# FMC_HPC1.net
KiCad netlist of a schematic drawn in Altium Designer
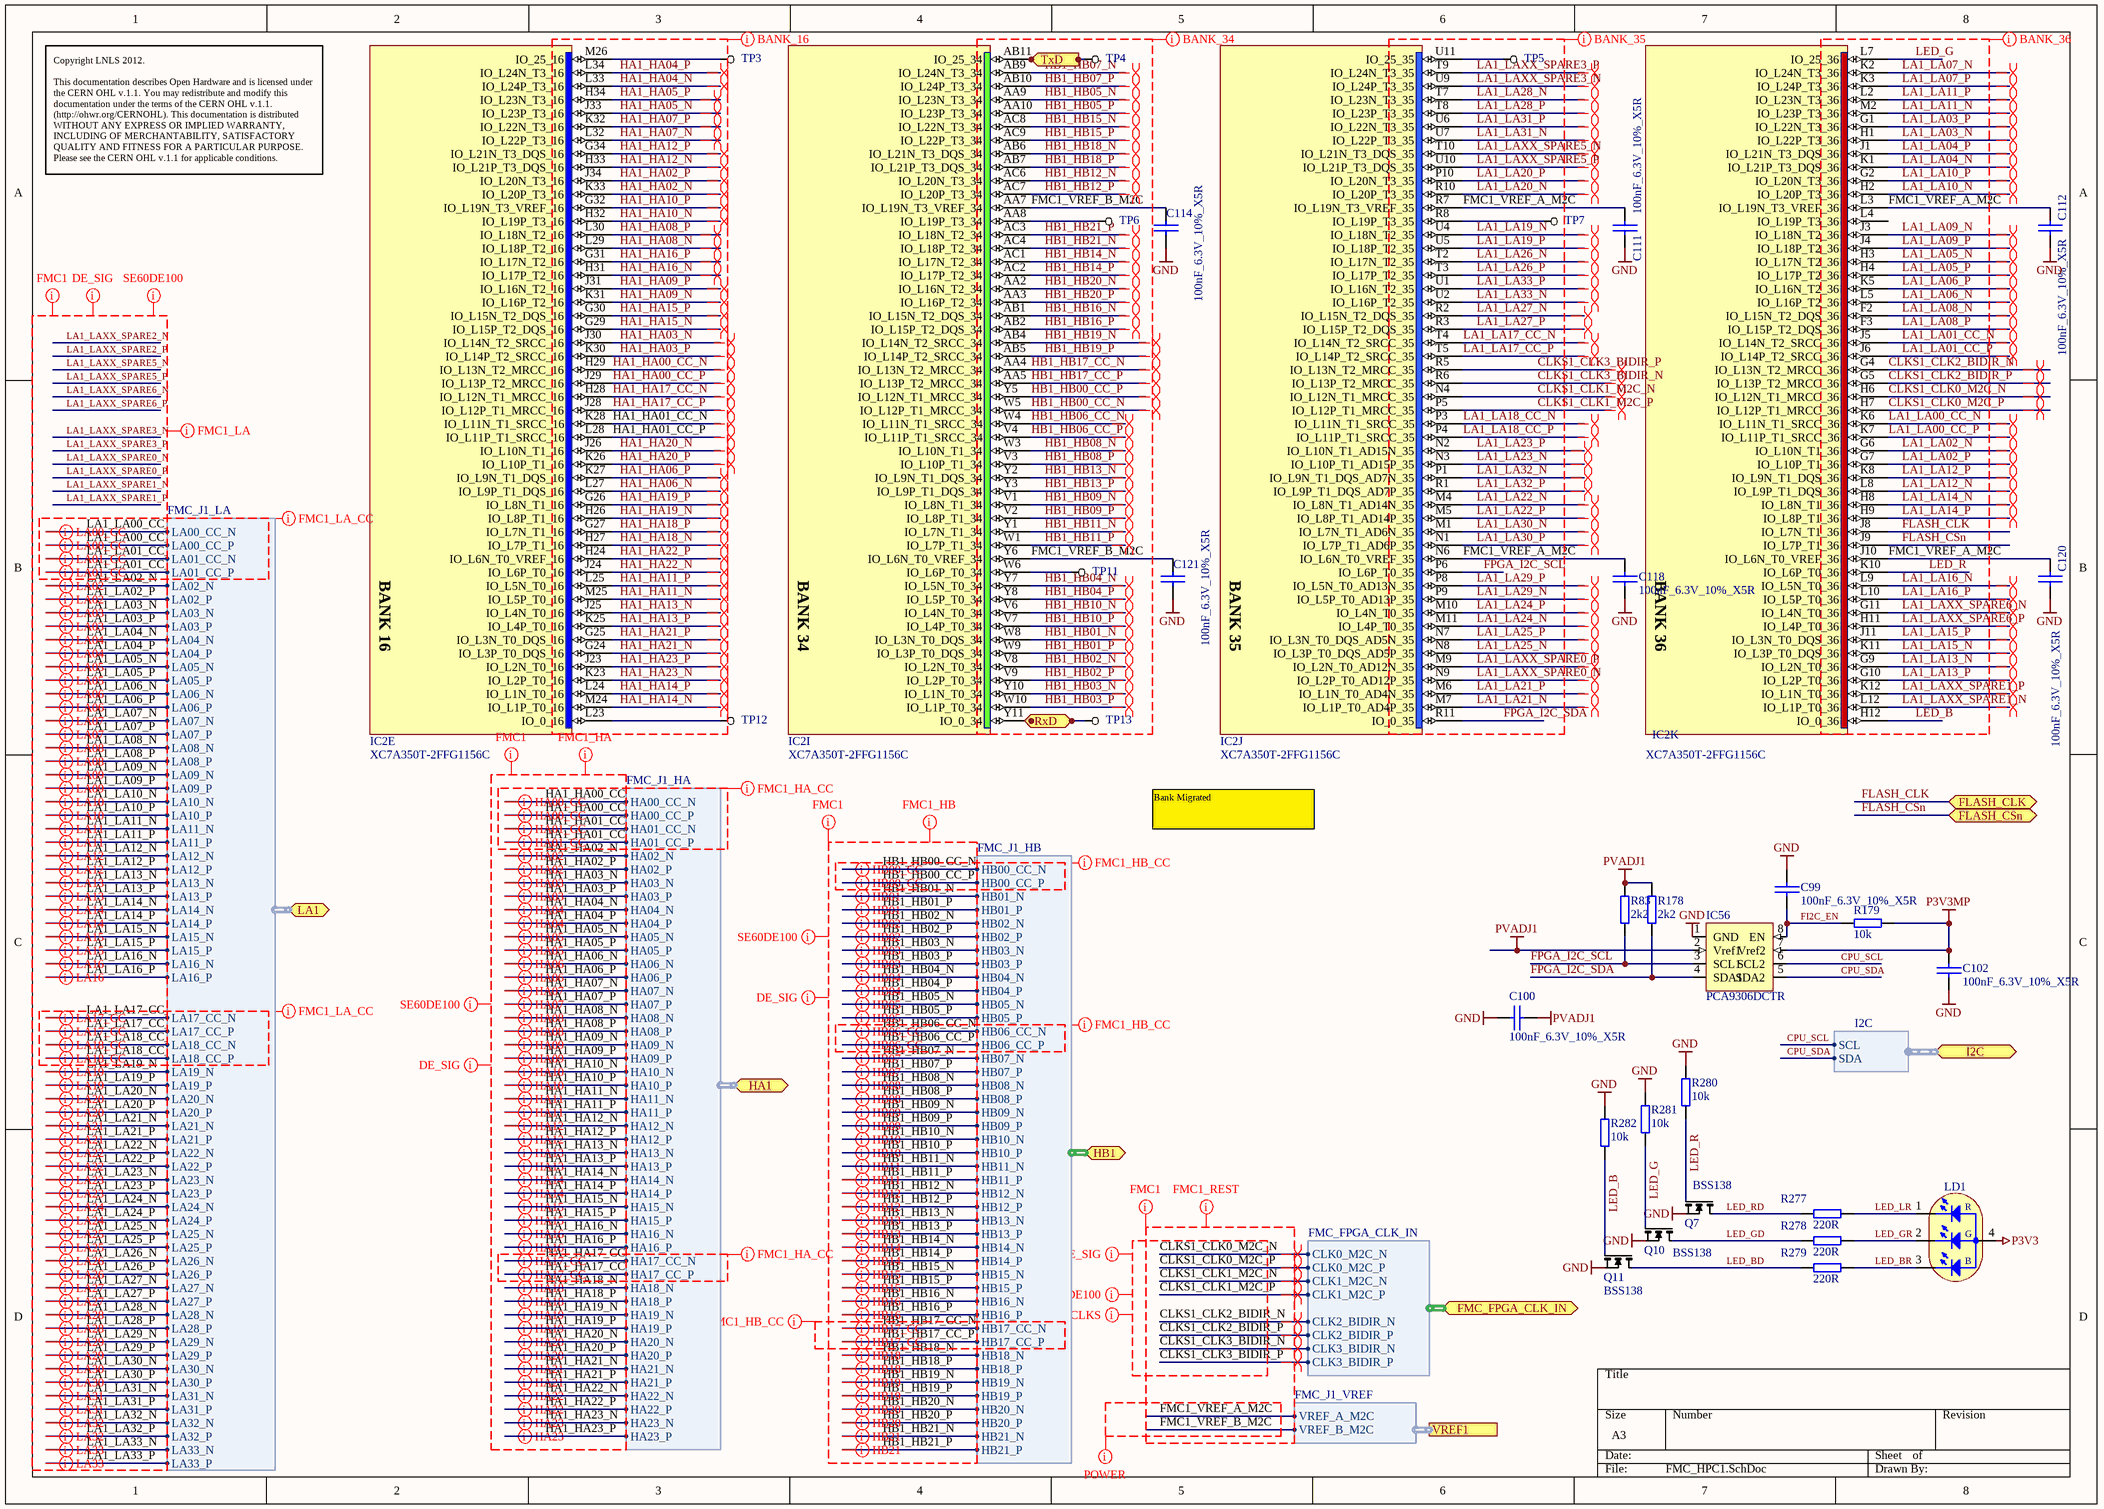
[diagram p0: FMC_HPC1.SchDoc]

(export (version "E")
  (design (tool "Eeschema 10.0.6"))
  (components
    (comp (ref "C99")
      (value "100nF_6.3V_10%_X5R")
      (footprint "0201C")
      (description "Capacitor SMD")
      (libsource (lib "LIBRARY_SCH") (part "CAP_SMD_0201"))
    )
    (comp (ref "C100")
      (value "100nF_6.3V_10%_X5R")
      (footprint "0201C")
      (description "Capacitor SMD")
      (libsource (lib "LIBRARY_SCH") (part "CAP_SMD_0201"))
    )
    (comp (ref "C102")
      (value "100nF_6.3V_10%_X5R")
      (footprint "0201C")
      (description "Capacitor SMD")
      (libsource (lib "LIBRARY_SCH") (part "CAP_SMD_0201"))
    )
    (comp (ref "C111")
      (value "100nF_6.3V_10%_X5R")
      (footprint "0201C")
      (description "Capacitor SMD")
      (libsource (lib "LIBRARY_SCH") (part "CAP_SMD_0201"))
    )
    (comp (ref "C112")
      (value "100nF_6.3V_10%_X5R")
      (footprint "0201C")
      (description "Capacitor SMD")
      (libsource (lib "LIBRARY_SCH") (part "CAP_SMD_0201"))
    )
    (comp (ref "C114")
      (value "100nF_6.3V_10%_X5R")
      (footprint "0201C")
      (description "Capacitor SMD")
      (libsource (lib "LIBRARY_SCH") (part "CAP_SMD_0201"))
    )
    (comp (ref "C118")
      (value "100nF_6.3V_10%_X5R")
      (footprint "0201C")
      (description "Capacitor SMD")
      (libsource (lib "LIBRARY_SCH") (part "CAP_SMD_0201"))
    )
    (comp (ref "C120")
      (value "100nF_6.3V_10%_X5R")
      (footprint "0201C")
      (description "Capacitor SMD")
      (libsource (lib "LIBRARY_SCH") (part "CAP_SMD_0201"))
    )
    (comp (ref "C121")
      (value "100nF_6.3V_10%_X5R")
      (footprint "0201C")
      (description "Capacitor SMD")
      (libsource (lib "LIBRARY_SCH") (part "CAP_SMD_0201"))
    )
    (comp (ref "IC2")
      (value "XC7A350T-2FFG1156C")
      (footprint "BGA1156C100P34X34_3500X3500X335")
      (description "Artix-6 FPGA, 16 GTPs, 600 User I/Os, 1156-Pin BGA, Speed Grade 2, Commercial Grade, Pb-Free")
      (fields (field (name "MANUFACTURER") "XILINX") (field (name "AUTHOR") "CERN DEM JLC"))
      (libsource (lib "AMC_FMC_Carrier") (part "XC7A350T-2FFG1156C"))
    )
    (comp (ref "IC56")
      (value "PCA9306DCTR")
      (footprint "SSOP8")
      (description "I2C BUS VOLTAGE-LEVEL TRANSLATOR")
      (libsource (lib "LIBRARY_SCH") (part "IFC_PCA9306"))
    )
    (comp (ref "LD1")
      (value "Red/Green/Blue")
      (footprint "LED_OPTEK_OVSRRGBCC3_a")
      (description "Right Angle Tricolor (RGB) Surface Mount LED, Body 3.2x1mm")
      (fields
        (field (name "PART NUMBER") "LED_OPTEK_OVSRRGBCC3_a")
        (field (name "MANUFACTURER") "OPTEK / TT ELECTRONICS")
        (field (name "AUTHOR") "CERN DEM JLC")
      )
      (libsource (lib "ICs And Semiconductors") (part "LED_OPTEK_OVSRRGBCC3"))
    )
    (comp (ref "Q7") (value "BSS138") (footprint "SOT-23") (libsource (lib "LIBRARY_SCH") (part "Q_BSS138")))
    (comp (ref "Q10") (value "BSS138") (footprint "SOT-23") (libsource (lib "LIBRARY_SCH") (part "Q_BSS138")))
    (comp (ref "Q11") (value "BSS138") (footprint "SOT-23") (libsource (lib "LIBRARY_SCH") (part "Q_BSS138")))
    (comp (ref "R83")
      (value "2k2")
      (footprint "0402R")
      (description "SMD Resistor")
      (libsource (lib "LIBRARY_SCH") (part "RES_0402"))
    )
    (comp (ref "R178")
      (value "2k2")
      (footprint "0402R")
      (description "SMD Resistor")
      (libsource (lib "LIBRARY_SCH") (part "RES_0402"))
    )
    (comp (ref "R179")
      (value "10k")
      (footprint "0402R")
      (description "SMD Resistor")
      (libsource (lib "LIBRARY_SCH") (part "RES_0402"))
    )
    (comp (ref "R277")
      (value "220R")
      (footprint "0402R")
      (description "SMD Resistor")
      (libsource (lib "LIBRARY_SCH") (part "RES_0402"))
    )
    (comp (ref "R278")
      (value "220R")
      (footprint "0402R")
      (description "SMD Resistor")
      (libsource (lib "LIBRARY_SCH") (part "RES_0402"))
    )
    (comp (ref "R279")
      (value "220R")
      (footprint "0402R")
      (description "SMD Resistor")
      (libsource (lib "LIBRARY_SCH") (part "RES_0402"))
    )
    (comp (ref "R280")
      (value "10k")
      (footprint "0402R")
      (description "SMD Resistor")
      (libsource (lib "LIBRARY_SCH") (part "RES_0402"))
    )
    (comp (ref "R281")
      (value "10k")
      (footprint "0402R")
      (description "SMD Resistor")
      (libsource (lib "LIBRARY_SCH") (part "RES_0402"))
    )
    (comp (ref "R282")
      (value "10k")
      (footprint "0402R")
      (description "SMD Resistor")
      (libsource (lib "LIBRARY_SCH") (part "RES_0402"))
    )
    (comp (ref "TP3")
      (value "TP")
      (footprint "TP_large")
      (description "Testpoint")
      (libsource (lib "LIBRARY_SCH") (part "TP"))
    )
    (comp (ref "TP4")
      (value "TP")
      (footprint "TP_large")
      (description "Testpoint")
      (libsource (lib "LIBRARY_SCH") (part "TP"))
    )
    (comp (ref "TP5")
      (value "TP")
      (footprint "TP_large")
      (description "Testpoint")
      (libsource (lib "LIBRARY_SCH") (part "TP"))
    )
    (comp (ref "TP6")
      (value "TP")
      (footprint "TP_large")
      (description "Testpoint")
      (libsource (lib "LIBRARY_SCH") (part "TP"))
    )
    (comp (ref "TP7")
      (value "TP")
      (footprint "TP_large")
      (description "Testpoint")
      (libsource (lib "LIBRARY_SCH") (part "TP"))
    )
    (comp (ref "TP11")
      (value "TP")
      (footprint "TP_large")
      (description "Testpoint")
      (libsource (lib "LIBRARY_SCH") (part "TP"))
    )
    (comp (ref "TP12")
      (value "TP")
      (footprint "TP_large")
      (description "Testpoint")
      (libsource (lib "LIBRARY_SCH") (part "TP"))
    )
    (comp (ref "TP13")
      (value "TP")
      (footprint "TP_large")
      (description "Testpoint")
      (libsource (lib "LIBRARY_SCH") (part "TP"))
    )
  )
  (nets
    (net (code "7") (name "/CLKS1_CLK0_M2C_N") (class "Default")
      (node (ref "IC2") (pin "H6") (pinfunction "IO_L12N_T1_MRCC_36_H6") (pintype "bidirectional"))
    )
    (net (code "8") (name "/CLKS1_CLK0_M2C_P") (class "Default")
      (node (ref "IC2") (pin "H7") (pinfunction "IO_L12P_T1_MRCC_36_H7") (pintype "bidirectional"))
    )
    (net (code "9") (name "/CLKS1_CLK1_M2C_N") (class "Default")
      (node (ref "IC2") (pin "N4") (pinfunction "IO_L12N_T1_MRCC_35_N4") (pintype "bidirectional"))
    )
    (net (code "10") (name "/CLKS1_CLK1_M2C_P") (class "Default")
      (node (ref "IC2") (pin "P5") (pinfunction "IO_L12P_T1_MRCC_35_P5") (pintype "bidirectional"))
    )
    (net (code "11") (name "/CLKS1_CLK2_BIDIR_N") (class "Default")
      (node (ref "IC2") (pin "G4") (pinfunction "IO_L13N_T2_MRCC_36_G4") (pintype "bidirectional"))
    )
    (net (code "12") (name "/CLKS1_CLK2_BIDIR_P") (class "Default")
      (node (ref "IC2") (pin "G5") (pinfunction "IO_L13P_T2_MRCC_36_G5") (pintype "bidirectional"))
    )
    (net (code "13") (name "/CLKS1_CLK3_BIDIR_N") (class "Default")
      (node (ref "IC2") (pin "R6") (pinfunction "IO_L13P_T2_MRCC_35_R6") (pintype "bidirectional"))
    )
    (net (code "14") (name "/CLKS1_CLK3_BIDIR_P") (class "Default")
      (node (ref "IC2") (pin "R5") (pinfunction "IO_L13N_T2_MRCC_35_R5") (pintype "bidirectional"))
    )
    (net (code "15") (name "/CPU_SCL") (class "Default")
      (node (ref "IC56") (pin "6") (pinfunction "SCL2_6") (pintype "bidirectional"))
    )
    (net (code "16") (name "/CPU_SDA") (class "Default")
      (node (ref "IC56") (pin "5") (pinfunction "SDA2_5") (pintype "bidirectional"))
    )
    (net (code "17") (name "/FI2C_EN") (class "Default")
      (node (ref "C99") (pin "1") (pinfunction "1_1") (pintype "passive"))
      (node (ref "IC56") (pin "8") (pinfunction "EN_8") (pintype "input"))
      (node (ref "R179") (pin "1") (pinfunction "1_1") (pintype "passive"))
    )
    (net (code "18") (name "/FLASH_CLK") (class "Default")
      (node (ref "IC2") (pin "J8") (pinfunction "IO_L7N_T1_36_J8") (pintype "bidirectional"))
    )
    (net (code "19") (name "/FLASH_CSn") (class "Default")
      (node (ref "IC2") (pin "J9") (pinfunction "IO_L7P_T1_36_J9") (pintype "bidirectional"))
    )
    (net (code "20") (name "/FMC1_VREF_A_M2C") (class "Default")
      (node (ref "C111") (pin "1") (pinfunction "1_1") (pintype "passive"))
      (node (ref "C112") (pin "1") (pinfunction "1_1") (pintype "passive"))
      (node (ref "C118") (pin "1") (pinfunction "1_1") (pintype "passive"))
      (node (ref "C120") (pin "1") (pinfunction "1_1") (pintype "passive"))
      (node (ref "IC2") (pin "J10") (pinfunction "IO_L6N_T0_VREF_36_J10") (pintype "bidirectional"))
      (node (ref "IC2") (pin "L3") (pinfunction "IO_L19N_T3_VREF_36_L3") (pintype "bidirectional"))
      (node (ref "IC2") (pin "N6") (pinfunction "IO_L6N_T0_VREF_35_N6") (pintype "bidirectional"))
      (node (ref "IC2") (pin "R7") (pinfunction "IO_L19N_T3_VREF_35_R7") (pintype "bidirectional"))
    )
    (net (code "21") (name "/FMC1_VREF_B_M2C") (class "Default")
      (node (ref "C114") (pin "1") (pinfunction "1_1") (pintype "passive"))
      (node (ref "C121") (pin "1") (pinfunction "1_1") (pintype "passive"))
      (node (ref "IC2") (pin "AA7") (pinfunction "IO_L19N_T3_VREF_34_AA7") (pintype "bidirectional"))
      (node (ref "IC2") (pin "Y6") (pinfunction "IO_L6N_T0_VREF_34_Y6") (pintype "bidirectional"))
    )
    (net (code "22") (name "/FPGA_I2C_SCL") (class "Default")
      (node (ref "IC2") (pin "P6") (pinfunction "IO_L6P_T0_35_P6") (pintype "bidirectional"))
      (node (ref "IC56") (pin "3") (pinfunction "SCL1_3") (pintype "bidirectional"))
      (node (ref "R83") (pin "1") (pinfunction "1_1") (pintype "passive"))
    )
    (net (code "23") (name "/FPGA_I2C_SDA") (class "Default")
      (node (ref "IC2") (pin "R11") (pinfunction "IO_0_35_R11") (pintype "bidirectional"))
      (node (ref "IC56") (pin "4") (pinfunction "SDA1_4") (pintype "bidirectional"))
      (node (ref "R178") (pin "1") (pinfunction "1_1") (pintype "passive"))
    )
    (net (code "24") (name "/HA1_HA00_CC_N") (class "Default")
      (node (ref "IC2") (pin "H29") (pinfunction "IO_L13N_T2_MRCC_16_H29") (pintype "bidirectional"))
    )
    (net (code "25") (name "/HA1_HA00_CC_P") (class "Default")
      (node (ref "IC2") (pin "J29") (pinfunction "IO_L13P_T2_MRCC_16_J29") (pintype "bidirectional"))
    )
    (net (code "26") (name "/HA1_HA01_CC_N") (class "Default")
      (node (ref "IC2") (pin "K28") (pinfunction "IO_L11N_T1_SRCC_16_K28") (pintype "bidirectional"))
    )
    (net (code "27") (name "/HA1_HA01_CC_P") (class "Default")
      (node (ref "IC2") (pin "L28") (pinfunction "IO_L11P_T1_SRCC_16_L28") (pintype "bidirectional"))
    )
    (net (code "28") (name "/HA1_HA02_N") (class "Default")
      (node (ref "IC2") (pin "K33") (pinfunction "IO_L20P_T3_16_K33") (pintype "bidirectional"))
    )
    (net (code "29") (name "/HA1_HA02_P") (class "Default")
      (node (ref "IC2") (pin "J34") (pinfunction "IO_L20N_T3_16_J34") (pintype "bidirectional"))
    )
    (net (code "30") (name "/HA1_HA03_N") (class "Default")
      (node (ref "IC2") (pin "J30") (pinfunction "IO_L14N_T2_SRCC_16_J30") (pintype "bidirectional"))
    )
    (net (code "31") (name "/HA1_HA03_P") (class "Default")
      (node (ref "IC2") (pin "K30") (pinfunction "IO_L14P_T2_SRCC_16_K30") (pintype "bidirectional"))
    )
    (net (code "32") (name "/HA1_HA04_N") (class "Default")
      (node (ref "IC2") (pin "L33") (pinfunction "IO_L24P_T3_16_L33") (pintype "bidirectional"))
    )
    (net (code "33") (name "/HA1_HA04_P") (class "Default")
      (node (ref "IC2") (pin "L34") (pinfunction "IO_L24N_T3_16_L34") (pintype "bidirectional"))
    )
    (net (code "34") (name "/HA1_HA05_N") (class "Default")
      (node (ref "IC2") (pin "J33") (pinfunction "IO_L23P_T3_16_J33") (pintype "bidirectional"))
    )
    (net (code "35") (name "/HA1_HA05_P") (class "Default")
      (node (ref "IC2") (pin "H34") (pinfunction "IO_L23N_T3_16_H34") (pintype "bidirectional"))
    )
    (net (code "36") (name "/HA1_HA06_N") (class "Default")
      (node (ref "IC2") (pin "L27") (pinfunction "IO_L9P_T1_DQS_16_L27") (pintype "bidirectional"))
    )
    (net (code "37") (name "/HA1_HA06_P") (class "Default")
      (node (ref "IC2") (pin "K27") (pinfunction "IO_L9N_T1_DQS_16_K27") (pintype "bidirectional"))
    )
    (net (code "38") (name "/HA1_HA07_N") (class "Default")
      (node (ref "IC2") (pin "L32") (pinfunction "IO_L22P_T3_16_L32") (pintype "bidirectional"))
    )
    (net (code "39") (name "/HA1_HA07_P") (class "Default")
      (node (ref "IC2") (pin "K32") (pinfunction "IO_L22N_T3_16_K32") (pintype "bidirectional"))
    )
    (net (code "40") (name "/HA1_HA08_N") (class "Default")
      (node (ref "IC2") (pin "L29") (pinfunction "IO_L18P_T2_16_L29") (pintype "bidirectional"))
    )
    (net (code "41") (name "/HA1_HA08_P") (class "Default")
      (node (ref "IC2") (pin "L30") (pinfunction "IO_L18N_T2_16_L30") (pintype "bidirectional"))
    )
    (net (code "42") (name "/HA1_HA09_N") (class "Default")
      (node (ref "IC2") (pin "K31") (pinfunction "IO_L16P_T2_16_K31") (pintype "bidirectional"))
    )
    (net (code "43") (name "/HA1_HA09_P") (class "Default")
      (node (ref "IC2") (pin "J31") (pinfunction "IO_L16N_T2_16_J31") (pintype "bidirectional"))
    )
    (net (code "44") (name "/HA1_HA10_N") (class "Default")
      (node (ref "IC2") (pin "H32") (pinfunction "IO_L19P_T3_16_H32") (pintype "bidirectional"))
    )
    (net (code "45") (name "/HA1_HA10_P") (class "Default")
      (node (ref "IC2") (pin "G32") (pinfunction "IO_L19N_T3_VREF_16_G32") (pintype "bidirectional"))
    )
    (net (code "46") (name "/HA1_HA11_N") (class "Default")
      (node (ref "IC2") (pin "M25") (pinfunction "IO_L5P_T0_16_M25") (pintype "bidirectional"))
    )
    (net (code "47") (name "/HA1_HA11_P") (class "Default")
      (node (ref "IC2") (pin "L25") (pinfunction "IO_L5N_T0_16_L25") (pintype "bidirectional"))
    )
    (net (code "48") (name "/HA1_HA12_N") (class "Default")
      (node (ref "IC2") (pin "H33") (pinfunction "IO_L21P_T3_DQS_16_H33") (pintype "bidirectional"))
    )
    (net (code "49") (name "/HA1_HA12_P") (class "Default")
      (node (ref "IC2") (pin "G34") (pinfunction "IO_L21N_T3_DQS_16_G34") (pintype "bidirectional"))
    )
    (net (code "50") (name "/HA1_HA13_N") (class "Default")
      (node (ref "IC2") (pin "J25") (pinfunction "IO_L4N_T0_16_J25") (pintype "bidirectional"))
    )
    (net (code "51") (name "/HA1_HA13_P") (class "Default")
      (node (ref "IC2") (pin "K25") (pinfunction "IO_L4P_T0_16_K25") (pintype "bidirectional"))
    )
    (net (code "52") (name "/HA1_HA14_N") (class "Default")
      (node (ref "IC2") (pin "M24") (pinfunction "IO_L1P_T0_16_M24") (pintype "bidirectional"))
    )
    (net (code "53") (name "/HA1_HA14_P") (class "Default")
      (node (ref "IC2") (pin "L24") (pinfunction "IO_L1N_T0_16_L24") (pintype "bidirectional"))
    )
    (net (code "54") (name "/HA1_HA15_N") (class "Default")
      (node (ref "IC2") (pin "G29") (pinfunction "IO_L15P_T2_DQS_16_G29") (pintype "bidirectional"))
    )
    (net (code "55") (name "/HA1_HA15_P") (class "Default")
      (node (ref "IC2") (pin "G30") (pinfunction "IO_L15N_T2_DQS_16_G30") (pintype "bidirectional"))
    )
    (net (code "56") (name "/HA1_HA16_N") (class "Default")
      (node (ref "IC2") (pin "H31") (pinfunction "IO_L17P_T2_16_H31") (pintype "bidirectional"))
    )
    (net (code "57") (name "/HA1_HA16_P") (class "Default")
      (node (ref "IC2") (pin "G31") (pinfunction "IO_L17N_T2_16_G31") (pintype "bidirectional"))
    )
    (net (code "58") (name "/HA1_HA17_CC_N") (class "Default")
      (node (ref "IC2") (pin "H28") (pinfunction "IO_L12N_T1_MRCC_16_H28") (pintype "bidirectional"))
    )
    (net (code "59") (name "/HA1_HA17_CC_P") (class "Default")
      (node (ref "IC2") (pin "J28") (pinfunction "IO_L12P_T1_MRCC_16_J28") (pintype "bidirectional"))
    )
    (net (code "60") (name "/HA1_HA18_N") (class "Default")
      (node (ref "IC2") (pin "H27") (pinfunction "IO_L7P_T1_16_H27") (pintype "bidirectional"))
    )
    (net (code "61") (name "/HA1_HA18_P") (class "Default")
      (node (ref "IC2") (pin "G27") (pinfunction "IO_L7N_T1_16_G27") (pintype "bidirectional"))
    )
    (net (code "62") (name "/HA1_HA19_N") (class "Default")
      (node (ref "IC2") (pin "H26") (pinfunction "IO_L8P_T1_16_H26") (pintype "bidirectional"))
    )
    (net (code "63") (name "/HA1_HA19_P") (class "Default")
      (node (ref "IC2") (pin "G26") (pinfunction "IO_L8N_T1_16_G26") (pintype "bidirectional"))
    )
    (net (code "64") (name "/HA1_HA20_N") (class "Default")
      (node (ref "IC2") (pin "J26") (pinfunction "IO_L10N_T1_16_J26") (pintype "bidirectional"))
    )
    (net (code "65") (name "/HA1_HA20_P") (class "Default")
      (node (ref "IC2") (pin "K26") (pinfunction "IO_L10P_T1_16_K26") (pintype "bidirectional"))
    )
    (net (code "66") (name "/HA1_HA21_N") (class "Default")
      (node (ref "IC2") (pin "G24") (pinfunction "IO_L3P_T0_DQS_16_G24") (pintype "bidirectional"))
    )
    (net (code "67") (name "/HA1_HA21_P") (class "Default")
      (node (ref "IC2") (pin "G25") (pinfunction "IO_L3N_T0_DQS_16_G25") (pintype "bidirectional"))
    )
    (net (code "68") (name "/HA1_HA22_N") (class "Default")
      (node (ref "IC2") (pin "J24") (pinfunction "IO_L6P_T0_16_J24") (pintype "bidirectional"))
    )
    (net (code "69") (name "/HA1_HA22_P") (class "Default")
      (node (ref "IC2") (pin "H24") (pinfunction "IO_L6N_T0_VREF_16_H24") (pintype "bidirectional"))
    )
    (net (code "70") (name "/HA1_HA23_N") (class "Default")
      (node (ref "IC2") (pin "K23") (pinfunction "IO_L2P_T0_16_K23") (pintype "bidirectional"))
    )
    (net (code "71") (name "/HA1_HA23_P") (class "Default")
      (node (ref "IC2") (pin "J23") (pinfunction "IO_L2N_T0_16_J23") (pintype "bidirectional"))
    )
    (net (code "72") (name "/HB1_HB00_CC_N") (class "Default")
      (node (ref "IC2") (pin "W5") (pinfunction "IO_L12P_T1_MRCC_34_W5") (pintype "bidirectional"))
    )
    (net (code "73") (name "/HB1_HB00_CC_P") (class "Default")
      (node (ref "IC2") (pin "Y5") (pinfunction "IO_L12N_T1_MRCC_34_Y5") (pintype "bidirectional"))
    )
    (net (code "74") (name "/HB1_HB01_N") (class "Default")
      (node (ref "IC2") (pin "W8") (pinfunction "IO_L3N_T0_DQS_34_W8") (pintype "bidirectional"))
    )
    (net (code "75") (name "/HB1_HB01_P") (class "Default")
      (node (ref "IC2") (pin "W9") (pinfunction "IO_L3P_T0_DQS_34_W9") (pintype "bidirectional"))
    )
    (net (code "76") (name "/HB1_HB02_N") (class "Default")
      (node (ref "IC2") (pin "V8") (pinfunction "IO_L2N_T0_34_V8") (pintype "bidirectional"))
    )
    (net (code "77") (name "/HB1_HB02_P") (class "Default")
      (node (ref "IC2") (pin "V9") (pinfunction "IO_L2P_T0_34_V9") (pintype "bidirectional"))
    )
    (net (code "78") (name "/HB1_HB03_N") (class "Default")
      (node (ref "IC2") (pin "Y10") (pinfunction "IO_L1N_T0_34_Y10") (pintype "bidirectional"))
    )
    (net (code "79") (name "/HB1_HB03_P") (class "Default")
      (node (ref "IC2") (pin "W10") (pinfunction "IO_L1P_T0_34_W10") (pintype "bidirectional"))
    )
    (net (code "80") (name "/HB1_HB04_N") (class "Default")
      (node (ref "IC2") (pin "Y7") (pinfunction "IO_L5N_T0_34_Y7") (pintype "bidirectional"))
    )
    (net (code "81") (name "/HB1_HB04_P") (class "Default")
      (node (ref "IC2") (pin "Y8") (pinfunction "IO_L5P_T0_34_Y8") (pintype "bidirectional"))
    )
    (net (code "82") (name "/HB1_HB05_N") (class "Default")
      (node (ref "IC2") (pin "AA9") (pinfunction "IO_L23N_T3_34_AA9") (pintype "bidirectional"))
    )
    (net (code "83") (name "/HB1_HB05_P") (class "Default")
      (node (ref "IC2") (pin "AA10") (pinfunction "IO_L23P_T3_34_AA10") (pintype "bidirectional"))
    )
    (net (code "84") (name "/HB1_HB06_CC_N") (class "Default")
      (node (ref "IC2") (pin "W4") (pinfunction "IO_L11N_T1_SRCC_34_W4") (pintype "bidirectional"))
    )
    (net (code "85") (name "/HB1_HB06_CC_P") (class "Default")
      (node (ref "IC2") (pin "V4") (pinfunction "IO_L11P_T1_SRCC_34_V4") (pintype "bidirectional"))
    )
    (net (code "86") (name "/HB1_HB07_N") (class "Default")
      (node (ref "IC2") (pin "AB9") (pinfunction "IO_L24N_T3_34_AB9") (pintype "bidirectional"))
    )
    (net (code "87") (name "/HB1_HB07_P") (class "Default")
      (node (ref "IC2") (pin "AB10") (pinfunction "IO_L24P_T3_34_AB10") (pintype "bidirectional"))
    )
    (net (code "88") (name "/HB1_HB08_N") (class "Default")
      (node (ref "IC2") (pin "W3") (pinfunction "IO_L10N_T1_34_W3") (pintype "bidirectional"))
    )
    (net (code "89") (name "/HB1_HB08_P") (class "Default")
      (node (ref "IC2") (pin "V3") (pinfunction "IO_L10P_T1_34_V3") (pintype "bidirectional"))
    )
    (net (code "90") (name "/HB1_HB09_N") (class "Default")
      (node (ref "IC2") (pin "V1") (pinfunction "IO_L8N_T1_34_V1") (pintype "bidirectional"))
    )
    (net (code "91") (name "/HB1_HB09_P") (class "Default")
      (node (ref "IC2") (pin "V2") (pinfunction "IO_L8P_T1_34_V2") (pintype "bidirectional"))
    )
    (net (code "92") (name "/HB1_HB10_N") (class "Default")
      (node (ref "IC2") (pin "V6") (pinfunction "IO_L4N_T0_34_V6") (pintype "bidirectional"))
    )
    (net (code "93") (name "/HB1_HB10_P") (class "Default")
      (node (ref "IC2") (pin "V7") (pinfunction "IO_L4P_T0_34_V7") (pintype "bidirectional"))
    )
    (net (code "94") (name "/HB1_HB11_N") (class "Default")
      (node (ref "IC2") (pin "Y1") (pinfunction "IO_L7N_T1_34_Y1") (pintype "bidirectional"))
    )
    (net (code "95") (name "/HB1_HB11_P") (class "Default")
      (node (ref "IC2") (pin "W1") (pinfunction "IO_L7P_T1_34_W1") (pintype "bidirectional"))
    )
    (net (code "96") (name "/HB1_HB12_N") (class "Default")
      (node (ref "IC2") (pin "AC6") (pinfunction "IO_L20N_T3_34_AC6") (pintype "bidirectional"))
    )
    (net (code "97") (name "/HB1_HB12_P") (class "Default")
      (node (ref "IC2") (pin "AC7") (pinfunction "IO_L20P_T3_34_AC7") (pintype "bidirectional"))
    )
    (net (code "98") (name "/HB1_HB13_N") (class "Default")
      (node (ref "IC2") (pin "Y2") (pinfunction "IO_L9N_T1_DQS_34_Y2") (pintype "bidirectional"))
    )
    (net (code "99") (name "/HB1_HB13_P") (class "Default")
      (node (ref "IC2") (pin "Y3") (pinfunction "IO_L9P_T1_DQS_34_Y3") (pintype "bidirectional"))
    )
    (net (code "100") (name "/HB1_HB14_N") (class "Default")
      (node (ref "IC2") (pin "AC1") (pinfunction "IO_L17N_T2_34_AC1") (pintype "bidirectional"))
    )
    (net (code "101") (name "/HB1_HB14_P") (class "Default")
      (node (ref "IC2") (pin "AC2") (pinfunction "IO_L17P_T2_34_AC2") (pintype "bidirectional"))
    )
    (net (code "102") (name "/HB1_HB15_N") (class "Default")
      (node (ref "IC2") (pin "AC8") (pinfunction "IO_L22N_T3_34_AC8") (pintype "bidirectional"))
    )
    (net (code "103") (name "/HB1_HB15_P") (class "Default")
      (node (ref "IC2") (pin "AC9") (pinfunction "IO_L22P_T3_34_AC9") (pintype "bidirectional"))
    )
    (net (code "104") (name "/HB1_HB16_N") (class "Default")
      (node (ref "IC2") (pin "AB1") (pinfunction "IO_L15N_T2_DQS_34_AB1") (pintype "bidirectional"))
    )
    (net (code "105") (name "/HB1_HB16_P") (class "Default")
      (node (ref "IC2") (pin "AB2") (pinfunction "IO_L15P_T2_DQS_34_AB2") (pintype "bidirectional"))
    )
    (net (code "106") (name "/HB1_HB17_CC_N") (class "Default")
      (node (ref "IC2") (pin "AA4") (pinfunction "IO_L13N_T2_MRCC_34_AA4") (pintype "bidirectional"))
    )
    (net (code "107") (name "/HB1_HB17_CC_P") (class "Default")
      (node (ref "IC2") (pin "AA5") (pinfunction "IO_L13P_T2_MRCC_34_AA5") (pintype "bidirectional"))
    )
    (net (code "108") (name "/HB1_HB18_N") (class "Default")
      (node (ref "IC2") (pin "AB6") (pinfunction "IO_L21N_T3_DQS_34_AB6") (pintype "bidirectional"))
    )
    (net (code "109") (name "/HB1_HB18_P") (class "Default")
      (node (ref "IC2") (pin "AB7") (pinfunction "IO_L21P_T3_DQS_34_AB7") (pintype "bidirectional"))
    )
    (net (code "110") (name "/HB1_HB19_N") (class "Default")
      (node (ref "IC2") (pin "AB4") (pinfunction "IO_L14N_T2_SRCC_34_AB4") (pintype "bidirectional"))
    )
    (net (code "111") (name "/HB1_HB19_P") (class "Default")
      (node (ref "IC2") (pin "AB5") (pinfunction "IO_L14P_T2_SRCC_34_AB5") (pintype "bidirectional"))
    )
    (net (code "112") (name "/HB1_HB20_N") (class "Default")
      (node (ref "IC2") (pin "AA2") (pinfunction "IO_L16N_T2_34_AA2") (pintype "bidirectional"))
    )
    (net (code "113") (name "/HB1_HB20_P") (class "Default")
      (node (ref "IC2") (pin "AA3") (pinfunction "IO_L16P_T2_34_AA3") (pintype "bidirectional"))
    )
    (net (code "114") (name "/HB1_HB21_N") (class "Default")
      (node (ref "IC2") (pin "AC4") (pinfunction "IO_L18P_T2_34_AC4") (pintype "bidirectional"))
    )
    (net (code "115") (name "/HB1_HB21_P") (class "Default")
      (node (ref "IC2") (pin "AC3") (pinfunction "IO_L18N_T2_34_AC3") (pintype "bidirectional"))
    )
    (net (code "116") (name "/LA1_LA00_CC_N") (class "Default")
      (node (ref "IC2") (pin "K6") (pinfunction "IO_L11N_T1_SRCC_36_K6") (pintype "bidirectional"))
    )
    (net (code "117") (name "/LA1_LA00_CC_P") (class "Default")
      (node (ref "IC2") (pin "K7") (pinfunction "IO_L11P_T1_SRCC_36_K7") (pintype "bidirectional"))
    )
    (net (code "118") (name "/LA1_LA01_CC_N") (class "Default")
      (node (ref "IC2") (pin "J5") (pinfunction "IO_L14N_T2_SRCC_36_J5") (pintype "bidirectional"))
    )
    (net (code "119") (name "/LA1_LA01_CC_P") (class "Default")
      (node (ref "IC2") (pin "J6") (pinfunction "IO_L14P_T2_SRCC_36_J6") (pintype "bidirectional"))
    )
    (net (code "120") (name "/LA1_LA02_N") (class "Default")
      (node (ref "IC2") (pin "G6") (pinfunction "IO_L10N_T1_36_G6") (pintype "bidirectional"))
    )
    (net (code "121") (name "/LA1_LA02_P") (class "Default")
      (node (ref "IC2") (pin "G7") (pinfunction "IO_L10P_T1_36_G7") (pintype "bidirectional"))
    )
    (net (code "122") (name "/LA1_LA03_N") (class "Default")
      (node (ref "IC2") (pin "H1") (pinfunction "IO_L22P_T3_36_H1") (pintype "bidirectional"))
    )
    (net (code "123") (name "/LA1_LA03_P") (class "Default")
      (node (ref "IC2") (pin "G1") (pinfunction "IO_L22N_T3_36_G1") (pintype "bidirectional"))
    )
    (net (code "124") (name "/LA1_LA04_N") (class "Default")
      (node (ref "IC2") (pin "K1") (pinfunction "IO_L21P_T3_DQS_36_K1") (pintype "bidirectional"))
    )
    (net (code "125") (name "/LA1_LA04_P") (class "Default")
      (node (ref "IC2") (pin "J1") (pinfunction "IO_L21N_T3_DQS_36_J1") (pintype "bidirectional"))
    )
    (net (code "126") (name "/LA1_LA05_N") (class "Default")
      (node (ref "IC2") (pin "H3") (pinfunction "IO_L17N_T2_36_H3") (pintype "bidirectional"))
    )
    (net (code "127") (name "/LA1_LA05_P") (class "Default")
      (node (ref "IC2") (pin "H4") (pinfunction "IO_L17P_T2_36_H4") (pintype "bidirectional"))
    )
    (net (code "128") (name "/LA1_LA06_N") (class "Default")
      (node (ref "IC2") (pin "L5") (pinfunction "IO_L16P_T2_36_L5") (pintype "bidirectional"))
    )
    (net (code "129") (name "/LA1_LA06_P") (class "Default")
      (node (ref "IC2") (pin "K5") (pinfunction "IO_L16N_T2_36_K5") (pintype "bidirectional"))
    )
    (net (code "130") (name "/LA1_LA07_N") (class "Default")
      (node (ref "IC2") (pin "K2") (pinfunction "IO_L24N_T3_36_K2") (pintype "bidirectional"))
    )
    (net (code "131") (name "/LA1_LA07_P") (class "Default")
      (node (ref "IC2") (pin "K3") (pinfunction "IO_L24P_T3_36_K3") (pintype "bidirectional"))
    )
    (net (code "132") (name "/LA1_LA08_N") (class "Default")
      (node (ref "IC2") (pin "F2") (pinfunction "IO_L15N_T2_DQS_36_F2") (pintype "bidirectional"))
    )
    (net (code "133") (name "/LA1_LA08_P") (class "Default")
      (node (ref "IC2") (pin "F3") (pinfunction "IO_L15P_T2_DQS_36_F3") (pintype "bidirectional"))
    )
    (net (code "134") (name "/LA1_LA09_N") (class "Default")
      (node (ref "IC2") (pin "J3") (pinfunction "IO_L18N_T2_36_J3") (pintype "bidirectional"))
    )
    (net (code "135") (name "/LA1_LA09_P") (class "Default")
      (node (ref "IC2") (pin "J4") (pinfunction "IO_L18P_T2_36_J4") (pintype "bidirectional"))
    )
    (net (code "136") (name "/LA1_LA10_N") (class "Default")
      (node (ref "IC2") (pin "H2") (pinfunction "IO_L20P_T3_36_H2") (pintype "bidirectional"))
    )
    (net (code "137") (name "/LA1_LA10_P") (class "Default")
      (node (ref "IC2") (pin "G2") (pinfunction "IO_L20N_T3_36_G2") (pintype "bidirectional"))
    )
    (net (code "138") (name "/LA1_LA11_N") (class "Default")
      (node (ref "IC2") (pin "M2") (pinfunction "IO_L23P_T3_36_M2") (pintype "bidirectional"))
    )
    (net (code "139") (name "/LA1_LA11_P") (class "Default")
      (node (ref "IC2") (pin "L2") (pinfunction "IO_L23N_T3_36_L2") (pintype "bidirectional"))
    )
    (net (code "140") (name "/LA1_LA12_N") (class "Default")
      (node (ref "IC2") (pin "L8") (pinfunction "IO_L9P_T1_DQS_36_L8") (pintype "bidirectional"))
    )
    (net (code "141") (name "/LA1_LA12_P") (class "Default")
      (node (ref "IC2") (pin "K8") (pinfunction "IO_L9N_T1_DQS_36_K8") (pintype "bidirectional"))
    )
    (net (code "142") (name "/LA1_LA13_N") (class "Default")
      (node (ref "IC2") (pin "G9") (pinfunction "IO_L2N_T0_36_G9") (pintype "bidirectional"))
    )
    (net (code "143") (name "/LA1_LA13_P") (class "Default")
      (node (ref "IC2") (pin "G10") (pinfunction "IO_L2P_T0_36_G10") (pintype "bidirectional"))
    )
    (net (code "144") (name "/LA1_LA14_N") (class "Default")
      (node (ref "IC2") (pin "H8") (pinfunction "IO_L8N_T1_36_H8") (pintype "bidirectional"))
    )
    (net (code "145") (name "/LA1_LA14_P") (class "Default")
      (node (ref "IC2") (pin "H9") (pinfunction "IO_L8P_T1_36_H9") (pintype "bidirectional"))
    )
    (net (code "146") (name "/LA1_LA15_N") (class "Default")
      (node (ref "IC2") (pin "K11") (pinfunction "IO_L3P_T0_DQS_36_K11") (pintype "bidirectional"))
    )
    (net (code "147") (name "/LA1_LA15_P") (class "Default")
      (node (ref "IC2") (pin "J11") (pinfunction "IO_L3N_T0_DQS_36_J11") (pintype "bidirectional"))
    )
    (net (code "148") (name "/LA1_LA16_N") (class "Default")
      (node (ref "IC2") (pin "L9") (pinfunction "IO_L5N_T0_36_L9") (pintype "bidirectional"))
    )
    (net (code "149") (name "/LA1_LA16_P") (class "Default")
      (node (ref "IC2") (pin "L10") (pinfunction "IO_L5P_T0_36_L10") (pintype "bidirectional"))
    )
    (net (code "150") (name "/LA1_LA17_CC_N") (class "Default")
      (node (ref "IC2") (pin "T4") (pinfunction "IO_L14N_T2_SRCC_35_T4") (pintype "bidirectional"))
    )
    (net (code "151") (name "/LA1_LA17_CC_P") (class "Default")
      (node (ref "IC2") (pin "T5") (pinfunction "IO_L14P_T2_SRCC_35_T5") (pintype "bidirectional"))
    )
    (net (code "152") (name "/LA1_LA18_CC_N") (class "Default")
      (node (ref "IC2") (pin "P3") (pinfunction "IO_L11N_T1_SRCC_35_P3") (pintype "bidirectional"))
    )
    (net (code "153") (name "/LA1_LA18_CC_P") (class "Default")
      (node (ref "IC2") (pin "P4") (pinfunction "IO_L11P_T1_SRCC_35_P4") (pintype "bidirectional"))
    )
    (net (code "154") (name "/LA1_LA19_N") (class "Default")
      (node (ref "IC2") (pin "U4") (pinfunction "IO_L18N_T2_35_U4") (pintype "bidirectional"))
    )
    (net (code "155") (name "/LA1_LA19_P") (class "Default")
      (node (ref "IC2") (pin "U5") (pinfunction "IO_L18P_T2_35_U5") (pintype "bidirectional"))
    )
    (net (code "156") (name "/LA1_LA20_N") (class "Default")
      (node (ref "IC2") (pin "R10") (pinfunction "IO_L20P_T3_35_R10") (pintype "bidirectional"))
    )
    (net (code "157") (name "/LA1_LA20_P") (class "Default")
      (node (ref "IC2") (pin "P10") (pinfunction "IO_L20N_T3_35_P10") (pintype "bidirectional"))
    )
    (net (code "158") (name "/LA1_LA21_N") (class "Default")
      (node (ref "IC2") (pin "M7") (pinfunction "IO_L1P_T0_AD4P_35_M7") (pintype "bidirectional"))
    )
    (net (code "159") (name "/LA1_LA21_P") (class "Default")
      (node (ref "IC2") (pin "M6") (pinfunction "IO_L1N_T0_AD4N_35_M6") (pintype "bidirectional"))
    )
    (net (code "160") (name "/LA1_LA22_N") (class "Default")
      (node (ref "IC2") (pin "M4") (pinfunction "IO_L8N_T1_AD14N_35_M4") (pintype "bidirectional"))
    )
    (net (code "161") (name "/LA1_LA22_P") (class "Default")
      (node (ref "IC2") (pin "M5") (pinfunction "IO_L8P_T1_AD14P_35_M5") (pintype "bidirectional"))
    )
    (net (code "162") (name "/LA1_LA23_N") (class "Default")
      (node (ref "IC2") (pin "N3") (pinfunction "IO_L10P_T1_AD15P_35_N3") (pintype "bidirectional"))
    )
    (net (code "163") (name "/LA1_LA23_P") (class "Default")
      (node (ref "IC2") (pin "N2") (pinfunction "IO_L10N_T1_AD15N_35_N2") (pintype "bidirectional"))
    )
    (net (code "164") (name "/LA1_LA24_N") (class "Default")
      (node (ref "IC2") (pin "M11") (pinfunction "IO_L4P_T0_35_M11") (pintype "bidirectional"))
    )
    (net (code "165") (name "/LA1_LA24_P") (class "Default")
      (node (ref "IC2") (pin "M10") (pinfunction "IO_L4N_T0_35_M10") (pintype "bidirectional"))
    )
    (net (code "166") (name "/LA1_LA25_N") (class "Default")
      (node (ref "IC2") (pin "N8") (pinfunction "IO_L3P_T0_DQS_AD5P_35_N8") (pintype "bidirectional"))
    )
    (net (code "167") (name "/LA1_LA25_P") (class "Default")
      (node (ref "IC2") (pin "N7") (pinfunction "IO_L3N_T0_DQS_AD5N_35_N7") (pintype "bidirectional"))
    )
    (net (code "168") (name "/LA1_LA26_N") (class "Default")
      (node (ref "IC2") (pin "T2") (pinfunction "IO_L17N_T2_35_T2") (pintype "bidirectional"))
    )
    (net (code "169") (name "/LA1_LA26_P") (class "Default")
      (node (ref "IC2") (pin "T3") (pinfunction "IO_L17P_T2_35_T3") (pintype "bidirectional"))
    )
    (net (code "170") (name "/LA1_LA27_N") (class "Default")
      (node (ref "IC2") (pin "R2") (pinfunction "IO_L15N_T2_DQS_35_R2") (pintype "bidirectional"))
    )
    (net (code "171") (name "/LA1_LA27_P") (class "Default")
      (node (ref "IC2") (pin "R3") (pinfunction "IO_L15P_T2_DQS_35_R3") (pintype "bidirectional"))
    )
    (net (code "172") (name "/LA1_LA28_N") (class "Default")
      (node (ref "IC2") (pin "T7") (pinfunction "IO_L23N_T3_35_T7") (pintype "bidirectional"))
    )
    (net (code "173") (name "/LA1_LA28_P") (class "Default")
      (node (ref "IC2") (pin "T8") (pinfunction "IO_L23P_T3_35_T8") (pintype "bidirectional"))
    )
    (net (code "174") (name "/LA1_LA29_N") (class "Default")
      (node (ref "IC2") (pin "P9") (pinfunction "IO_L5P_T0_AD13P_35_P9") (pintype "bidirectional"))
    )
    (net (code "175") (name "/LA1_LA29_P") (class "Default")
      (node (ref "IC2") (pin "P8") (pinfunction "IO_L5N_T0_AD13N_35_P8") (pintype "bidirectional"))
    )
    (net (code "176") (name "/LA1_LA30_N") (class "Default")
      (node (ref "IC2") (pin "M1") (pinfunction "IO_L7N_T1_AD6N_35_M1") (pintype "bidirectional"))
    )
    (net (code "177") (name "/LA1_LA30_P") (class "Default")
      (node (ref "IC2") (pin "N1") (pinfunction "IO_L7P_T1_AD6P_35_N1") (pintype "bidirectional"))
    )
    (net (code "178") (name "/LA1_LA31_N") (class "Default")
      (node (ref "IC2") (pin "U7") (pinfunction "IO_L22P_T3_35_U7") (pintype "bidirectional"))
    )
    (net (code "179") (name "/LA1_LA31_P") (class "Default")
      (node (ref "IC2") (pin "U6") (pinfunction "IO_L22N_T3_35_U6") (pintype "bidirectional"))
    )
    (net (code "180") (name "/LA1_LA32_N") (class "Default")
      (node (ref "IC2") (pin "P1") (pinfunction "IO_L9N_T1_DQS_AD7N_35_P1") (pintype "bidirectional"))
    )
    (net (code "181") (name "/LA1_LA32_P") (class "Default")
      (node (ref "IC2") (pin "R1") (pinfunction "IO_L9P_T1_DQS_AD7P_35_R1") (pintype "bidirectional"))
    )
    (net (code "182") (name "/LA1_LA33_N") (class "Default")
      (node (ref "IC2") (pin "U2") (pinfunction "IO_L16P_T2_35_U2") (pintype "bidirectional"))
    )
    (net (code "183") (name "/LA1_LA33_P") (class "Default")
      (node (ref "IC2") (pin "U1") (pinfunction "IO_L16N_T2_35_U1") (pintype "bidirectional"))
    )
    (net (code "184") (name "/LA1_LAXX_SPARE0_N") (class "Default")
      (node (ref "IC2") (pin "N9") (pinfunction "IO_L2P_T0_AD12P_35_N9") (pintype "bidirectional"))
    )
    (net (code "185") (name "/LA1_LAXX_SPARE0_P") (class "Default")
      (node (ref "IC2") (pin "M9") (pinfunction "IO_L2N_T0_AD12N_35_M9") (pintype "bidirectional"))
    )
    (net (code "186") (name "/LA1_LAXX_SPARE1_N") (class "Default")
      (node (ref "IC2") (pin "L12") (pinfunction "IO_L1P_T0_36_L12") (pintype "bidirectional"))
    )
    (net (code "187") (name "/LA1_LAXX_SPARE1_P") (class "Default")
      (node (ref "IC2") (pin "K12") (pinfunction "IO_L1N_T0_36_K12") (pintype "bidirectional"))
    )
    (net (code "190") (name "/LA1_LAXX_SPARE3_N") (class "Default")
      (node (ref "IC2") (pin "U9") (pinfunction "IO_L24P_T3_35_U9") (pintype "bidirectional"))
    )
    (net (code "191") (name "/LA1_LAXX_SPARE3_P") (class "Default")
      (node (ref "IC2") (pin "T9") (pinfunction "IO_L24N_T3_35_T9") (pintype "bidirectional"))
    )
    (net (code "192") (name "/LA1_LAXX_SPARE5_N") (class "Default")
      (node (ref "IC2") (pin "T10") (pinfunction "IO_L21N_T3_DQS_35_T10") (pintype "bidirectional"))
    )
    (net (code "193") (name "/LA1_LAXX_SPARE5_P") (class "Default")
      (node (ref "IC2") (pin "U10") (pinfunction "IO_L21P_T3_DQS_35_U10") (pintype "bidirectional"))
    )
    (net (code "194") (name "/LA1_LAXX_SPARE6_N") (class "Default")
      (node (ref "IC2") (pin "G11") (pinfunction "IO_L4N_T0_36_G11") (pintype "bidirectional"))
    )
    (net (code "195") (name "/LA1_LAXX_SPARE6_P") (class "Default")
      (node (ref "IC2") (pin "H11") (pinfunction "IO_L4P_T0_36_H11") (pintype "bidirectional"))
    )
    (net (code "196") (name "/LED_B") (class "Default")
      (node (ref "IC2") (pin "H12") (pinfunction "IO_0_36_H12") (pintype "bidirectional"))
      (node (ref "Q11") (pin "1") (pinfunction "G_1") (pintype "input"))
      (node (ref "R282") (pin "2") (pinfunction "2_2") (pintype "passive"))
    )
    (net (code "197") (name "/LED_BD") (class "Default")
      (node (ref "Q11") (pin "3") (pinfunction "D_3") (pintype "passive"))
      (node (ref "R279") (pin "1") (pinfunction "1_1") (pintype "passive"))
    )
    (net (code "198") (name "/LED_BR") (class "Default")
      (node (ref "LD1") (pin "3") (pinfunction "AB_3") (pintype "passive"))
      (node (ref "R279") (pin "2") (pinfunction "2_2") (pintype "passive"))
    )
    (net (code "199") (name "/LED_G") (class "Default")
      (node (ref "IC2") (pin "L7") (pinfunction "IO_25_36_L7") (pintype "bidirectional"))
      (node (ref "Q10") (pin "1") (pinfunction "G_1") (pintype "input"))
      (node (ref "R281") (pin "2") (pinfunction "2_2") (pintype "passive"))
    )
    (net (code "200") (name "/LED_GD") (class "Default")
      (node (ref "Q10") (pin "3") (pinfunction "D_3") (pintype "passive"))
      (node (ref "R278") (pin "1") (pinfunction "1_1") (pintype "passive"))
    )
    (net (code "201") (name "/LED_GR") (class "Default")
      (node (ref "LD1") (pin "2") (pinfunction "AG_2") (pintype "passive"))
      (node (ref "R278") (pin "2") (pinfunction "2_2") (pintype "passive"))
    )
    (net (code "202") (name "/LED_LR") (class "Default")
      (node (ref "LD1") (pin "1") (pinfunction "AR_1") (pintype "passive"))
      (node (ref "R277") (pin "2") (pinfunction "2_2") (pintype "passive"))
    )
    (net (code "203") (name "/LED_R") (class "Default")
      (node (ref "IC2") (pin "K10") (pinfunction "IO_L6P_T0_36_K10") (pintype "bidirectional"))
      (node (ref "Q7") (pin "1") (pinfunction "G_1") (pintype "input"))
      (node (ref "R280") (pin "2") (pinfunction "2_2") (pintype "passive"))
    )
    (net (code "204") (name "/LED_RD") (class "Default")
      (node (ref "Q7") (pin "3") (pinfunction "D_3") (pintype "passive"))
      (node (ref "R277") (pin "1") (pinfunction "1_1") (pintype "passive"))
    )
    (net (code "205") (name "/RxD") (class "Default")
      (node (ref "IC2") (pin "Y11") (pinfunction "IO_0_34_Y11") (pintype "bidirectional"))
      (node (ref "TP13") (pin "1") (pintype "passive"))
    )
    (net (code "206") (name "/TxD") (class "Default")
      (node (ref "IC2") (pin "AB11") (pinfunction "IO_25_34_AB11") (pintype "bidirectional"))
      (node (ref "TP4") (pin "1") (pintype "passive"))
    )
    (net (code "213") (name "GND") (class "Default")
      (node (ref "C100") (pin "2") (pinfunction "2_2") (pintype "passive"))
      (node (ref "C102") (pin "2") (pinfunction "2_2") (pintype "passive"))
      (node (ref "C111") (pin "2") (pinfunction "2_2") (pintype "passive"))
      (node (ref "C112") (pin "2") (pinfunction "2_2") (pintype "passive"))
      (node (ref "C114") (pin "2") (pinfunction "2_2") (pintype "passive"))
      (node (ref "C118") (pin "2") (pinfunction "2_2") (pintype "passive"))
      (node (ref "C120") (pin "2") (pinfunction "2_2") (pintype "passive"))
      (node (ref "C121") (pin "2") (pinfunction "2_2") (pintype "passive"))
      (node (ref "C99") (pin "2") (pinfunction "2_2") (pintype "passive"))
      (node (ref "IC56") (pin "1") (pinfunction "GND_1") (pintype "power_in"))
      (node (ref "Q10") (pin "2") (pinfunction "S_2") (pintype "passive"))
      (node (ref "Q11") (pin "2") (pinfunction "S_2") (pintype "passive"))
      (node (ref "Q7") (pin "2") (pinfunction "S_2") (pintype "passive"))
      (node (ref "R280") (pin "1") (pinfunction "1_1") (pintype "passive"))
      (node (ref "R281") (pin "1") (pinfunction "1_1") (pintype "passive"))
      (node (ref "R282") (pin "1") (pinfunction "1_1") (pintype "passive"))
    )
    (net (code "214") (name "Net-(IC2E-IO_0_16)") (class "Default")
      (node (ref "IC2") (pin "L23") (pinfunction "IO_0_16_L23") (pintype "bidirectional"))
      (node (ref "TP12") (pin "1") (pintype "passive"))
    )
    (net (code "215") (name "Net-(IC2E-IO_25_16)") (class "Default")
      (node (ref "IC2") (pin "M26") (pinfunction "IO_25_16_M26") (pintype "bidirectional"))
      (node (ref "TP3") (pin "1") (pintype "passive"))
    )
    (net (code "216") (name "Net-(IC2I-IO_L6P_T0_34)") (class "Default")
      (node (ref "IC2") (pin "W6") (pinfunction "IO_L6P_T0_34_W6") (pintype "bidirectional"))
      (node (ref "TP11") (pin "1") (pintype "passive"))
    )
    (net (code "217") (name "Net-(IC2I-IO_L19P_T3_34)") (class "Default")
      (node (ref "IC2") (pin "AA8") (pinfunction "IO_L19P_T3_34_AA8") (pintype "bidirectional"))
      (node (ref "TP6") (pin "1") (pintype "passive"))
    )
    (net (code "218") (name "Net-(IC2J-IO_25_35)") (class "Default")
      (node (ref "IC2") (pin "U11") (pinfunction "IO_25_35_U11") (pintype "bidirectional"))
      (node (ref "TP5") (pin "1") (pintype "passive"))
    )
    (net (code "219") (name "Net-(IC2J-IO_L19P_T3_35)") (class "Default")
      (node (ref "IC2") (pin "R8") (pinfunction "IO_L19P_T3_35_R8") (pintype "bidirectional"))
      (node (ref "TP7") (pin "1") (pintype "passive"))
    )
    (net (code "220") (name "P3V3") (class "Default")
      (node (ref "LD1") (pin "4") (pinfunction "CC_4") (pintype "passive"))
    )
    (net (code "221") (name "P3V3MP") (class "Default")
      (node (ref "C102") (pin "1") (pinfunction "1_1") (pintype "passive"))
      (node (ref "IC56") (pin "7") (pinfunction "Vref2_7") (pintype "input"))
      (node (ref "R179") (pin "2") (pinfunction "2_2") (pintype "passive"))
    )
    (net (code "222") (name "PVADJ1") (class "Default")
      (node (ref "C100") (pin "1") (pinfunction "1_1") (pintype "passive"))
      (node (ref "IC56") (pin "2") (pinfunction "Vref1_2") (pintype "input"))
      (node (ref "R178") (pin "2") (pinfunction "2_2") (pintype "passive"))
      (node (ref "R83") (pin "2") (pinfunction "2_2") (pintype "passive"))
    )
    (net (code "223") (name "unconnected-(IC2K-IO_L19P_T3_36-PadL4)") (class "Default")
      (node (ref "IC2") (pin "L4") (pinfunction "IO_L19P_T3_36_L4") (pintype "bidirectional"))
    )
  )
)
